# Schematic_STM32.net
KiCad netlist of a schematic drawn in Altium Designer
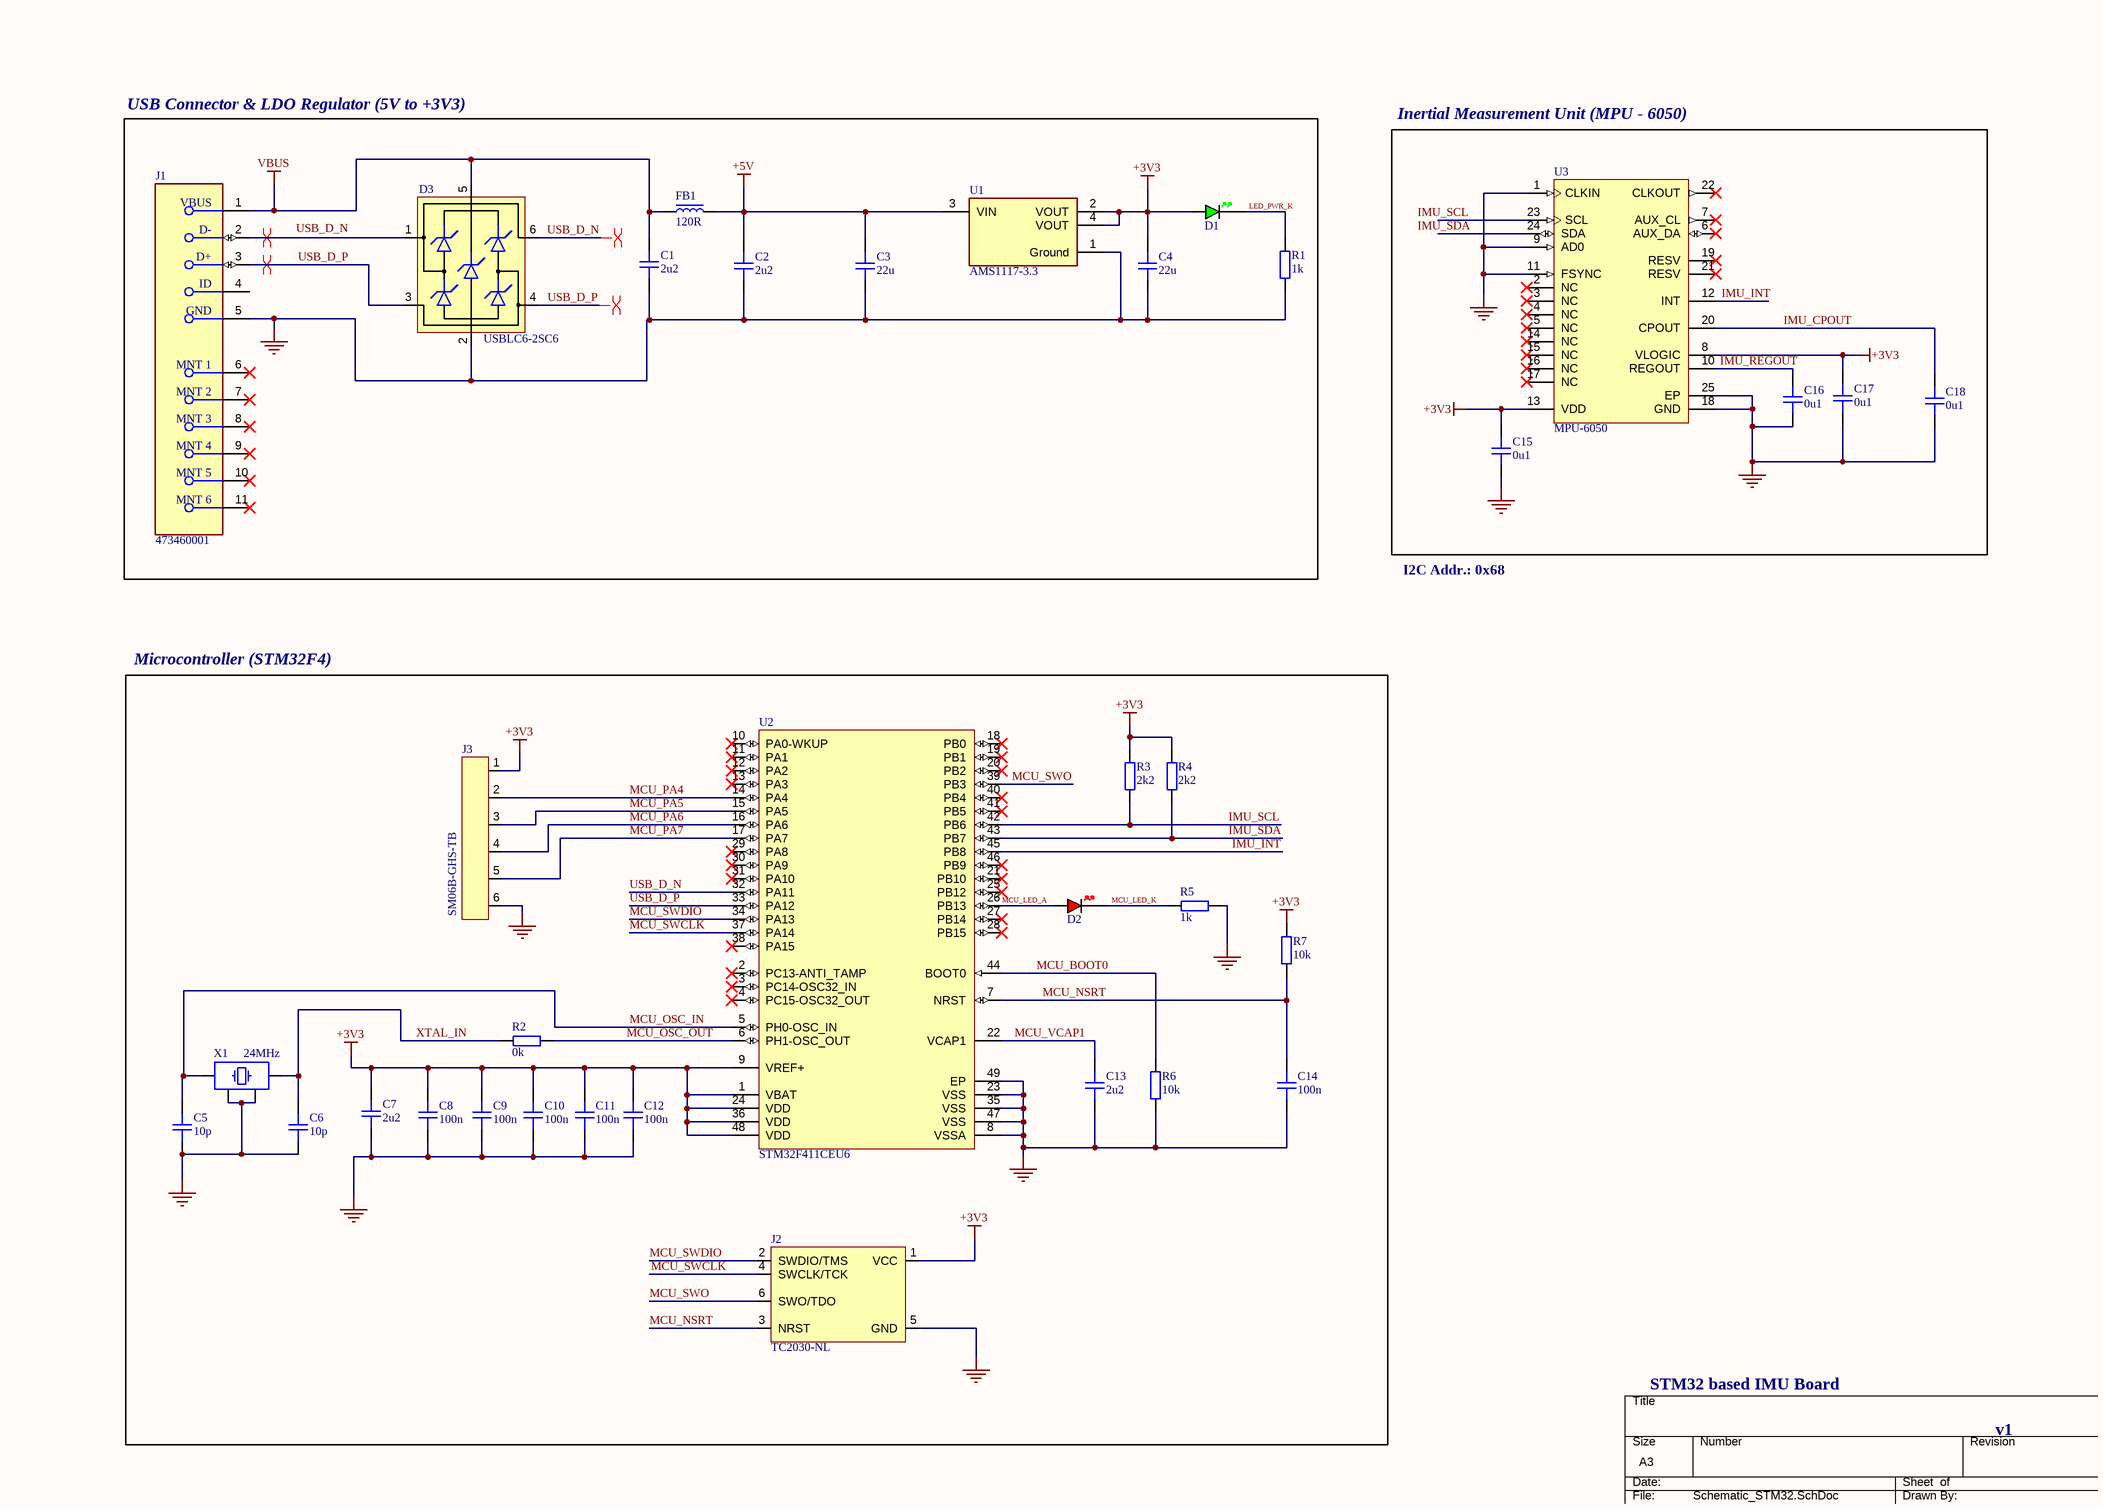
[diagram p0: Schematic_STM32.SchDoc]

(export (version "E")
  (design (tool "Eeschema 10.0.6"))
  (components
    (comp (ref "C1")
      (value "2u2")
      (footprint "CAP_0603")
      (description "Capacitor SMD 0603")
      (libsource (lib "Schematic-Lib-PhilsLab") (part "CAP_0603"))
    )
    (comp (ref "C2")
      (value "2u2")
      (footprint "CAP_0603")
      (description "Capacitor SMD 0603")
      (libsource (lib "Schematic-Lib-PhilsLab") (part "CAP_0603"))
    )
    (comp (ref "C3")
      (value "22u")
      (footprint "CAP_0805")
      (description "Capacitor SMD 0805")
      (libsource (lib "Schematic-Lib-PhilsLab") (part "CAP_0805"))
    )
    (comp (ref "C4")
      (value "22u")
      (footprint "CAP_0805")
      (description "Capacitor SMD 0805")
      (libsource (lib "Schematic-Lib-PhilsLab") (part "CAP_0805"))
    )
    (comp (ref "C5")
      (value "10p")
      (footprint "CAP_0402")
      (description "Capacitor SMD 0402")
      (libsource (lib "Schematic-Lib-PhilsLab") (part "CAP_0402"))
    )
    (comp (ref "C6")
      (value "10p")
      (footprint "CAP_0402")
      (description "Capacitor SMD 0402")
      (libsource (lib "Schematic-Lib-PhilsLab") (part "CAP_0402"))
    )
    (comp (ref "C7")
      (value "2u2")
      (footprint "CAP_0603")
      (description "Capacitor SMD 0603")
      (libsource (lib "Schematic-Lib-PhilsLab") (part "CAP_0603"))
    )
    (comp (ref "C8")
      (value "100n")
      (footprint "CAP_0402")
      (description "Capacitor SMD 0402")
      (libsource (lib "Schematic-Lib-PhilsLab") (part "CAP_0402"))
    )
    (comp (ref "C9")
      (value "100n")
      (footprint "CAP_0402")
      (description "Capacitor SMD 0402")
      (libsource (lib "Schematic-Lib-PhilsLab") (part "CAP_0402"))
    )
    (comp (ref "C10")
      (value "100n")
      (footprint "CAP_0402")
      (description "Capacitor SMD 0402")
      (libsource (lib "Schematic-Lib-PhilsLab") (part "CAP_0402"))
    )
    (comp (ref "C11")
      (value "100n")
      (footprint "CAP_0402")
      (description "Capacitor SMD 0402")
      (libsource (lib "Schematic-Lib-PhilsLab") (part "CAP_0402"))
    )
    (comp (ref "C12")
      (value "100n")
      (footprint "CAP_0402")
      (description "Capacitor SMD 0402")
      (libsource (lib "Schematic-Lib-PhilsLab") (part "CAP_0402"))
    )
    (comp (ref "C13")
      (value "2u2")
      (footprint "CAP_0603")
      (description "Capacitor SMD 0603")
      (libsource (lib "Schematic-Lib-PhilsLab") (part "CAP_0603"))
    )
    (comp (ref "C14")
      (value "100n")
      (footprint "CAP_0402")
      (description "Capacitor SMD 0402")
      (libsource (lib "Schematic-Lib-PhilsLab") (part "CAP_0402"))
    )
    (comp (ref "C15")
      (value "0u1")
      (footprint "CAP_0402")
      (description "Capacitor SMD 0402")
      (libsource (lib "Schematic-Lib-PhilsLab") (part "CAP_0402"))
    )
    (comp (ref "C16")
      (value "0u1")
      (footprint "CAP_0402")
      (description "Capacitor SMD 0402")
      (libsource (lib "Schematic-Lib-PhilsLab") (part "CAP_0402"))
    )
    (comp (ref "C17")
      (value "0u1")
      (footprint "CAP_0402")
      (description "Capacitor SMD 0402")
      (libsource (lib "Schematic-Lib-PhilsLab") (part "CAP_0402"))
    )
    (comp (ref "C18")
      (value "0u1")
      (footprint "CAP_0402")
      (description "Capacitor SMD 0402")
      (libsource (lib "Schematic-Lib-PhilsLab") (part "CAP_0402"))
    )
    (comp (ref "D1")
      (value "GREEN")
      (footprint "LED_0402_GREEN")
      (description "LED 0402 GREEN SMD")
      (libsource (lib "Schematic-Lib-PhilsLab") (part "LED_0402_GREEN"))
    )
    (comp (ref "D2")
      (value "RED")
      (footprint "LED_0402_RED")
      (description "LED 0402 RED SMD")
      (libsource (lib "Schematic-Lib-PhilsLab") (part "LED_0402_RED"))
    )
    (comp (ref "D3")
      (value "USBLC6-2SC6")
      (footprint "SOT-23-6")
      (description "Low-Capacitance ESD Protection USB")
      (fields (field (name "MANUFACTURER") "STMicroelectronics"))
      (libsource (lib "Schematic-Lib-PhilsLab") (part "USBLC6-2SC6"))
    )
    (comp (ref "FB1")
      (value "120R")
      (footprint "FB_0402")
      (description "Ferrite Bead SMD 0402")
      (libsource (lib "Schematic-Lib-PhilsLab") (part "FB_0402"))
    )
    (comp (ref "J1")
      (value "473460001")
      (footprint "FP-473460001-MFG")
      (description "CONN RCPT USB2.0 MICRO B SMD R/A")
      (fields
        (field (name "OCTOPART") "https://octopart.com/47346-0001-molex-7164928")
        (field (name "MANUFACTURER") "Molex")
      )
      (libsource (lib "Altium Content Vault") (part "53ae1f1d9b557310b43ca686e5bb76a"))
    )
    (comp (ref "J2")
      (value "TC2030-NL")
      (footprint "TC2030-NL-FP")
      (description "Tag-Connect No-Solder SWD Debug Connector (No Legs) DO NOT PLACE")
      (fields
        (field (name "MANUFACTURER") "Tag-Connect")
        (field (name "MANUFACTURER PART NUMBER") "TC2030-NL-FP")
      )
      (libsource (lib "Schematic-Lib-PhilsLab") (part "TC2030-NL"))
    )
    (comp (ref "J3")
      (value "SM06B-GHS-TB")
      (footprint "SM06B-GHS-TB")
      (description "Header Connector 6 Position 1.25MM Pitch SMD Horizontal JST GH")
      (fields (field (name "MANUFACTURER") "JST"))
      (libsource (lib "Schematic-Lib-PhilsLab") (part "SM06B-GHS-TB"))
    )
    (comp (ref "R1")
      (value "1k")
      (footprint "RES_0402")
      (description "Resistor SMD 0402")
      (libsource (lib "Schematic-Lib-PhilsLab") (part "RES_0402"))
    )
    (comp (ref "R2")
      (value "0k")
      (footprint "RES_0402")
      (description "Resistor SMD 0402")
      (libsource (lib "Schematic-Lib-PhilsLab") (part "RES_0402"))
    )
    (comp (ref "R3")
      (value "2k2")
      (footprint "RES_0402")
      (description "Resistor SMD 0402")
      (libsource (lib "Schematic-Lib-PhilsLab") (part "RES_0402"))
    )
    (comp (ref "R4")
      (value "2k2")
      (footprint "RES_0402")
      (description "Resistor SMD 0402")
      (libsource (lib "Schematic-Lib-PhilsLab") (part "RES_0402"))
    )
    (comp (ref "R5")
      (value "1k")
      (footprint "RES_0402")
      (description "Resistor SMD 0402")
      (libsource (lib "Schematic-Lib-PhilsLab") (part "RES_0402"))
    )
    (comp (ref "R6")
      (value "10k")
      (footprint "RES_0402")
      (description "Resistor SMD 0402")
      (libsource (lib "Schematic-Lib-PhilsLab") (part "RES_0402"))
    )
    (comp (ref "R7")
      (value "10k")
      (footprint "RES_0402")
      (description "Resistor SMD 0402")
      (libsource (lib "Schematic-Lib-PhilsLab") (part "RES_0402"))
    )
    (comp (ref "U1")
      (value "AMS1117-3.3")
      (footprint "FP-AMS1117-IPC_C")
      (description "LDO Voltage Regulators 1A, 3.3V")
      (fields
        (field (name "OCTOPART") "https://octopart.com/ams1117-3.3-advanced+monolithic+systems-25899300")
        (field (name "MANUFACTURER") "Advanced Monolithic Systems")
      )
      (libsource (lib "Altium Content Vault") (part "8bdbb5f8e77002000e30dd2845d0354"))
    )
    (comp (ref "U2")
      (value "STM32F411CEU6")
      (footprint "STM-UFQFPN48_L")
      (libsource (lib "Altium Content Vault") (part "MC-ARM-STM32F411-UFQFPN48"))
    )
    (comp (ref "U3")
      (value "MPU-6050")
      (footprint "IS-QFN-24_V")
      (fields (field (name "MANUFACTURER") "InvenSense"))
      (libsource (lib "Altium Content Vault") (part "IS-MPU-6050-QFN-24"))
    )
    (comp (ref "X1")
      (value "24MHz")
      (footprint "XTAL_3225")
      (description "Crystal SMD 24MHz 10PPM 7pF 3225")
      (fields
        (field (name "MANUFACTURER") "Epson")
        (field (name "MANUFACTURER PART NUMBER") "TSX-3225 24.0000MF15X-AC")
      )
      (libsource (lib "Schematic-Lib-PhilsLab") (part "TSX-3225_24.0000MF15X-AC"))
    )
  )
  (nets
    (net (code "1") (name "+3V3") (class "Default")
      (node (ref "C10") (pin "2") (pinfunction "2_2") (pintype "passive"))
      (node (ref "C11") (pin "2") (pinfunction "2_2") (pintype "passive"))
      (node (ref "C12") (pin "2") (pinfunction "2_2") (pintype "passive"))
      (node (ref "C15") (pin "2") (pinfunction "2_2") (pintype "passive"))
      (node (ref "C17") (pin "2") (pinfunction "2_2") (pintype "passive"))
      (node (ref "C4") (pin "2") (pinfunction "2_2") (pintype "passive"))
      (node (ref "C7") (pin "2") (pinfunction "2_2") (pintype "passive"))
      (node (ref "C8") (pin "2") (pinfunction "2_2") (pintype "passive"))
      (node (ref "C9") (pin "2") (pinfunction "2_2") (pintype "passive"))
      (node (ref "D1") (pin "A") (pinfunction "A_A") (pintype "passive"))
      (node (ref "J2") (pin "1") (pinfunction "VCC_1") (pintype "passive"))
      (node (ref "J3") (pin "1") (pinfunction "1_1") (pintype "passive"))
      (node (ref "R3") (pin "2") (pinfunction "2_2") (pintype "passive"))
      (node (ref "R4") (pin "2") (pinfunction "2_2") (pintype "passive"))
      (node (ref "R7") (pin "2") (pinfunction "2_2") (pintype "passive"))
      (node (ref "U1") (pin "2") (pinfunction "VOUT_2") (pintype "passive"))
      (node (ref "U1") (pin "4") (pinfunction "VOUT_4") (pintype "passive"))
      (node (ref "U2") (pin "1") (pinfunction "VBAT_1") (pintype "power_in"))
      (node (ref "U2") (pin "24") (pinfunction "VDD_24") (pintype "power_in"))
      (node (ref "U2") (pin "36") (pinfunction "VDD_36") (pintype "power_in"))
      (node (ref "U2") (pin "48") (pinfunction "VDD_48") (pintype "power_in"))
      (node (ref "U2") (pin "9") (pinfunction "VREF+_9") (pintype "power_in"))
      (node (ref "U3") (pin "13") (pinfunction "VDD_13") (pintype "power_in"))
      (node (ref "U3") (pin "8") (pinfunction "VLOGIC_8") (pintype "power_in"))
    )
    (net (code "2") (name "+5V") (class "Default")
      (node (ref "C2") (pin "2") (pinfunction "2_2") (pintype "passive"))
      (node (ref "C3") (pin "2") (pinfunction "2_2") (pintype "passive"))
      (node (ref "FB1") (pin "2") (pinfunction "2_2") (pintype "passive"))
      (node (ref "U1") (pin "3") (pinfunction "VIN_3") (pintype "power_in"))
    )
    (net (code "3") (name "/IMU_CPOUT") (class "Default")
      (node (ref "C18") (pin "2") (pinfunction "2_2") (pintype "passive"))
      (node (ref "U3") (pin "20") (pinfunction "CPOUT_20") (pintype "passive"))
    )
    (net (code "4") (name "/IMU_INT") (class "Default")
      (node (ref "U2") (pin "45") (pinfunction "PB8_45") (pintype "bidirectional"))
      (node (ref "U3") (pin "12") (pinfunction "INT_12") (pintype "open_collector"))
    )
    (net (code "5") (name "/IMU_REGOUT") (class "Default")
      (node (ref "C16") (pin "2") (pinfunction "2_2") (pintype "passive"))
      (node (ref "U3") (pin "10") (pinfunction "REGOUT_10") (pintype "passive"))
    )
    (net (code "6") (name "/IMU_SCL") (class "Default")
      (node (ref "R3") (pin "1") (pinfunction "1_1") (pintype "passive"))
      (node (ref "U2") (pin "42") (pinfunction "PB6_42") (pintype "bidirectional"))
      (node (ref "U3") (pin "23") (pinfunction "SCL_23") (pintype "input"))
    )
    (net (code "7") (name "/IMU_SDA") (class "Default")
      (node (ref "R4") (pin "1") (pinfunction "1_1") (pintype "passive"))
      (node (ref "U2") (pin "43") (pinfunction "PB7_43") (pintype "bidirectional"))
      (node (ref "U3") (pin "24") (pinfunction "SDA_24") (pintype "bidirectional"))
    )
    (net (code "8") (name "/LED_PWR_K") (class "Default")
      (node (ref "D1") (pin "K") (pinfunction "K_K") (pintype "passive"))
      (node (ref "R1") (pin "2") (pinfunction "2_2") (pintype "passive"))
    )
    (net (code "9") (name "/MCU_BOOT0") (class "Default")
      (node (ref "R6") (pin "2") (pinfunction "2_2") (pintype "passive"))
      (node (ref "U2") (pin "44") (pinfunction "BOOT0_44") (pintype "input"))
    )
    (net (code "10") (name "/MCU_LED_A") (class "Default")
      (node (ref "D2") (pin "A") (pinfunction "A_A") (pintype "passive"))
      (node (ref "U2") (pin "26") (pinfunction "PB13_26") (pintype "bidirectional"))
    )
    (net (code "11") (name "/MCU_LED_K") (class "Default")
      (node (ref "D2") (pin "K") (pinfunction "K_K") (pintype "passive"))
      (node (ref "R5") (pin "2") (pinfunction "2_2") (pintype "passive"))
    )
    (net (code "12") (name "/MCU_NSRT") (class "Default")
      (node (ref "C14") (pin "2") (pinfunction "2_2") (pintype "passive"))
      (node (ref "J2") (pin "3") (pinfunction "NRST_3") (pintype "passive"))
      (node (ref "R7") (pin "1") (pinfunction "1_1") (pintype "passive"))
      (node (ref "U2") (pin "7") (pinfunction "NRST_7") (pintype "bidirectional"))
    )
    (net (code "13") (name "/MCU_OSC_IN") (class "Default")
      (node (ref "C5") (pin "2") (pinfunction "2_2") (pintype "passive"))
      (node (ref "U2") (pin "5") (pinfunction "PH0-OSC_IN_5") (pintype "bidirectional"))
      (node (ref "X1") (pin "1") (pinfunction "1_1") (pintype "passive"))
    )
    (net (code "14") (name "/MCU_OSC_OUT") (class "Default")
      (node (ref "R2") (pin "1") (pinfunction "1_1") (pintype "passive"))
      (node (ref "U2") (pin "6") (pinfunction "PH1-OSC_OUT_6") (pintype "bidirectional"))
    )
    (net (code "15") (name "/MCU_PA4") (class "Default")
      (node (ref "J3") (pin "2") (pinfunction "2_2") (pintype "passive"))
      (node (ref "U2") (pin "14") (pinfunction "PA4_14") (pintype "bidirectional"))
    )
    (net (code "16") (name "/MCU_PA5") (class "Default")
      (node (ref "J3") (pin "3") (pinfunction "3_3") (pintype "passive"))
      (node (ref "U2") (pin "15") (pinfunction "PA5_15") (pintype "bidirectional"))
    )
    (net (code "17") (name "/MCU_PA6") (class "Default")
      (node (ref "J3") (pin "4") (pinfunction "4_4") (pintype "passive"))
      (node (ref "U2") (pin "16") (pinfunction "PA6_16") (pintype "bidirectional"))
    )
    (net (code "18") (name "/MCU_PA7") (class "Default")
      (node (ref "J3") (pin "5") (pinfunction "5_5") (pintype "passive"))
      (node (ref "U2") (pin "17") (pinfunction "PA7_17") (pintype "bidirectional"))
    )
    (net (code "19") (name "/MCU_SWCLK") (class "Default")
      (node (ref "J2") (pin "4") (pinfunction "SWCLK/TCK_4") (pintype "passive"))
      (node (ref "U2") (pin "37") (pinfunction "PA14_37") (pintype "bidirectional"))
    )
    (net (code "20") (name "/MCU_SWDIO") (class "Default")
      (node (ref "J2") (pin "2") (pinfunction "SWDIO/TMS_2") (pintype "passive"))
      (node (ref "U2") (pin "34") (pinfunction "PA13_34") (pintype "bidirectional"))
    )
    (net (code "21") (name "/MCU_SWO") (class "Default")
      (node (ref "J2") (pin "6") (pinfunction "SWO/TDO_6") (pintype "passive"))
      (node (ref "U2") (pin "39") (pinfunction "PB3_39") (pintype "bidirectional"))
    )
    (net (code "22") (name "/MCU_VCAP1") (class "Default")
      (node (ref "C13") (pin "2") (pinfunction "2_2") (pintype "passive"))
      (node (ref "U2") (pin "22") (pinfunction "VCAP1_22") (pintype "passive"))
    )
    (net (code "23") (name "/USB_D_N") (class "Default")
      (node (ref "D3") (pin "6") (pinfunction "IO1_6") (pintype "bidirectional"))
      (node (ref "U2") (pin "32") (pinfunction "PA11_32") (pintype "bidirectional"))
    )
    (net (code "24") (name "/USB_D_P") (class "Default")
      (node (ref "D3") (pin "3") (pinfunction "IO2_3") (pintype "bidirectional"))
      (node (ref "D3") (pin "4") (pinfunction "IO2_4") (pintype "bidirectional"))
      (node (ref "J1") (pin "3") (pinfunction "D+_3") (pintype "bidirectional"))
      (node (ref "U2") (pin "33") (pinfunction "PA12_33") (pintype "bidirectional"))
    )
    (net (code "25") (name "/XTAL_IN") (class "Default")
      (node (ref "C6") (pin "2") (pinfunction "2_2") (pintype "passive"))
      (node (ref "R2") (pin "2") (pinfunction "2_2") (pintype "passive"))
      (node (ref "X1") (pin "3") (pinfunction "3_3") (pintype "passive"))
    )
    (net (code "26") (name "GND") (class "Default")
      (node (ref "C1") (pin "1") (pinfunction "1_1") (pintype "passive"))
      (node (ref "C10") (pin "1") (pinfunction "1_1") (pintype "passive"))
      (node (ref "C11") (pin "1") (pinfunction "1_1") (pintype "passive"))
      (node (ref "C12") (pin "1") (pinfunction "1_1") (pintype "passive"))
      (node (ref "C13") (pin "1") (pinfunction "1_1") (pintype "passive"))
      (node (ref "C14") (pin "1") (pinfunction "1_1") (pintype "passive"))
      (node (ref "C15") (pin "1") (pinfunction "1_1") (pintype "passive"))
      (node (ref "C16") (pin "1") (pinfunction "1_1") (pintype "passive"))
      (node (ref "C17") (pin "1") (pinfunction "1_1") (pintype "passive"))
      (node (ref "C18") (pin "1") (pinfunction "1_1") (pintype "passive"))
      (node (ref "C2") (pin "1") (pinfunction "1_1") (pintype "passive"))
      (node (ref "C3") (pin "1") (pinfunction "1_1") (pintype "passive"))
      (node (ref "C4") (pin "1") (pinfunction "1_1") (pintype "passive"))
      (node (ref "C5") (pin "1") (pinfunction "1_1") (pintype "passive"))
      (node (ref "C6") (pin "1") (pinfunction "1_1") (pintype "passive"))
      (node (ref "C7") (pin "1") (pinfunction "1_1") (pintype "passive"))
      (node (ref "C8") (pin "1") (pinfunction "1_1") (pintype "passive"))
      (node (ref "C9") (pin "1") (pinfunction "1_1") (pintype "passive"))
      (node (ref "D3") (pin "2") (pinfunction "GND_2") (pintype "power_in"))
      (node (ref "J1") (pin "5") (pinfunction "GND_5") (pintype "power_in"))
      (node (ref "J2") (pin "5") (pinfunction "GND_5") (pintype "passive"))
      (node (ref "J3") (pin "6") (pinfunction "6_6") (pintype "passive"))
      (node (ref "R1") (pin "1") (pinfunction "1_1") (pintype "passive"))
      (node (ref "R5") (pin "1") (pinfunction "1_1") (pintype "passive"))
      (node (ref "R6") (pin "1") (pinfunction "1_1") (pintype "passive"))
      (node (ref "U1") (pin "1") (pinfunction "Ground_1") (pintype "power_in"))
      (node (ref "U2") (pin "23") (pinfunction "VSS_23") (pintype "power_in"))
      (node (ref "U2") (pin "35") (pinfunction "VSS_35") (pintype "power_in"))
      (node (ref "U2") (pin "47") (pinfunction "VSS_47") (pintype "power_in"))
      (node (ref "U2") (pin "49") (pinfunction "EP_49") (pintype "power_in"))
      (node (ref "U2") (pin "8") (pinfunction "VSSA_8") (pintype "power_in"))
      (node (ref "U3") (pin "1") (pinfunction "CLKIN_1") (pintype "input"))
      (node (ref "U3") (pin "11") (pinfunction "FSYNC_11") (pintype "input"))
      (node (ref "U3") (pin "18") (pinfunction "GND_18") (pintype "power_in"))
      (node (ref "U3") (pin "25") (pinfunction "EP_25") (pintype "power_in"))
      (node (ref "U3") (pin "9") (pinfunction "AD0_9") (pintype "input"))
      (node (ref "X1") (pin "2") (pinfunction "2_2") (pintype "passive"))
      (node (ref "X1") (pin "4") (pinfunction "4_4") (pintype "passive"))
    )
    (net (code "27") (name "Net-(J1-D-)") (class "Default")
      (node (ref "D3") (pin "1") (pinfunction "IO1_1") (pintype "bidirectional"))
      (node (ref "J1") (pin "2") (pinfunction "D-_2") (pintype "bidirectional"))
    )
    (net (code "28") (name "VBUS") (class "Default")
      (node (ref "C1") (pin "2") (pinfunction "2_2") (pintype "passive"))
      (node (ref "D3") (pin "5") (pinfunction "VBUS_5") (pintype "power_in"))
      (node (ref "FB1") (pin "1") (pinfunction "1_1") (pintype "passive"))
      (node (ref "J1") (pin "1") (pinfunction "VBUS_1") (pintype "power_in"))
    )
    (net (code "29") (name "unconnected-(J1-ID-Pad4)") (class "Default")
      (node (ref "J1") (pin "4") (pinfunction "ID_4") (pintype "passive"))
    )
    (net (code "30") (name "unconnected-(J1-MNT_1-Pad6)") (class "Default")
      (node (ref "J1") (pin "6") (pinfunction "MNT_1_6") (pintype "passive+no_connect"))
    )
    (net (code "31") (name "unconnected-(J1-MNT_2-Pad7)") (class "Default")
      (node (ref "J1") (pin "7") (pinfunction "MNT_2_7") (pintype "passive+no_connect"))
    )
    (net (code "32") (name "unconnected-(J1-MNT_3-Pad8)") (class "Default")
      (node (ref "J1") (pin "8") (pinfunction "MNT_3_8") (pintype "passive+no_connect"))
    )
    (net (code "33") (name "unconnected-(J1-MNT_4-Pad9)") (class "Default")
      (node (ref "J1") (pin "9") (pinfunction "MNT_4_9") (pintype "passive+no_connect"))
    )
    (net (code "34") (name "unconnected-(J1-MNT_5-Pad10)") (class "Default")
      (node (ref "J1") (pin "10") (pinfunction "MNT_5_10") (pintype "passive+no_connect"))
    )
    (net (code "35") (name "unconnected-(J1-MNT_6-Pad11)") (class "Default")
      (node (ref "J1") (pin "11") (pinfunction "MNT_6_11") (pintype "passive+no_connect"))
    )
    (net (code "36") (name "unconnected-(U2-PA0-WKUP-Pad10)") (class "Default")
      (node (ref "U2") (pin "10") (pinfunction "PA0-WKUP_10") (pintype "bidirectional+no_connect"))
    )
    (net (code "37") (name "unconnected-(U2-PA1-Pad11)") (class "Default")
      (node (ref "U2") (pin "11") (pinfunction "PA1_11") (pintype "bidirectional+no_connect"))
    )
    (net (code "38") (name "unconnected-(U2-PA2-Pad12)") (class "Default")
      (node (ref "U2") (pin "12") (pinfunction "PA2_12") (pintype "bidirectional+no_connect"))
    )
    (net (code "39") (name "unconnected-(U2-PA3-Pad13)") (class "Default")
      (node (ref "U2") (pin "13") (pinfunction "PA3_13") (pintype "bidirectional+no_connect"))
    )
    (net (code "40") (name "unconnected-(U2-PA8-Pad29)") (class "Default")
      (node (ref "U2") (pin "29") (pinfunction "PA8_29") (pintype "bidirectional+no_connect"))
    )
    (net (code "41") (name "unconnected-(U2-PA9-Pad30)") (class "Default")
      (node (ref "U2") (pin "30") (pinfunction "PA9_30") (pintype "bidirectional+no_connect"))
    )
    (net (code "42") (name "unconnected-(U2-PA10-Pad31)") (class "Default")
      (node (ref "U2") (pin "31") (pinfunction "PA10_31") (pintype "bidirectional+no_connect"))
    )
    (net (code "43") (name "unconnected-(U2-PA15-Pad38)") (class "Default")
      (node (ref "U2") (pin "38") (pinfunction "PA15_38") (pintype "bidirectional+no_connect"))
    )
    (net (code "44") (name "unconnected-(U2-PB0-Pad18)") (class "Default")
      (node (ref "U2") (pin "18") (pinfunction "PB0_18") (pintype "bidirectional+no_connect"))
    )
    (net (code "45") (name "unconnected-(U2-PB1-Pad19)") (class "Default")
      (node (ref "U2") (pin "19") (pinfunction "PB1_19") (pintype "bidirectional+no_connect"))
    )
    (net (code "46") (name "unconnected-(U2-PB2-Pad20)") (class "Default")
      (node (ref "U2") (pin "20") (pinfunction "PB2_20") (pintype "bidirectional+no_connect"))
    )
    (net (code "47") (name "unconnected-(U2-PB4-Pad40)") (class "Default")
      (node (ref "U2") (pin "40") (pinfunction "PB4_40") (pintype "bidirectional+no_connect"))
    )
    (net (code "48") (name "unconnected-(U2-PB5-Pad41)") (class "Default")
      (node (ref "U2") (pin "41") (pinfunction "PB5_41") (pintype "bidirectional+no_connect"))
    )
    (net (code "49") (name "unconnected-(U2-PB9-Pad46)") (class "Default")
      (node (ref "U2") (pin "46") (pinfunction "PB9_46") (pintype "bidirectional+no_connect"))
    )
    (net (code "50") (name "unconnected-(U2-PB10-Pad21)") (class "Default")
      (node (ref "U2") (pin "21") (pinfunction "PB10_21") (pintype "bidirectional+no_connect"))
    )
    (net (code "51") (name "unconnected-(U2-PB12-Pad25)") (class "Default")
      (node (ref "U2") (pin "25") (pinfunction "PB12_25") (pintype "bidirectional+no_connect"))
    )
    (net (code "52") (name "unconnected-(U2-PB14-Pad27)") (class "Default")
      (node (ref "U2") (pin "27") (pinfunction "PB14_27") (pintype "bidirectional+no_connect"))
    )
    (net (code "53") (name "unconnected-(U2-PB15-Pad28)") (class "Default")
      (node (ref "U2") (pin "28") (pinfunction "PB15_28") (pintype "bidirectional+no_connect"))
    )
    (net (code "54") (name "unconnected-(U2-PC13-ANTI_TAMP-Pad2)") (class "Default")
      (node (ref "U2") (pin "2") (pinfunction "PC13-ANTI_TAMP_2") (pintype "bidirectional+no_connect"))
    )
    (net (code "55") (name "unconnected-(U2-PC14-OSC32_IN-Pad3)") (class "Default")
      (node (ref "U2") (pin "3") (pinfunction "PC14-OSC32_IN_3") (pintype "bidirectional+no_connect"))
    )
    (net (code "56") (name "unconnected-(U2-PC15-OSC32_OUT-Pad4)") (class "Default")
      (node (ref "U2") (pin "4") (pinfunction "PC15-OSC32_OUT_4") (pintype "bidirectional+no_connect"))
    )
    (net (code "57") (name "unconnected-(U3-AUX_CL-Pad7)") (class "Default")
      (node (ref "U3") (pin "7") (pinfunction "AUX_CL_7") (pintype "output+no_connect"))
    )
    (net (code "58") (name "unconnected-(U3-AUX_DA-Pad6)") (class "Default")
      (node (ref "U3") (pin "6") (pinfunction "AUX_DA_6") (pintype "bidirectional+no_connect"))
    )
    (net (code "59") (name "unconnected-(U3-CLKOUT-Pad22)") (class "Default")
      (node (ref "U3") (pin "22") (pinfunction "CLKOUT_22") (pintype "output+no_connect"))
    )
    (net (code "60") (name "unconnected-(U3-NC-Pad2)") (class "Default")
      (node (ref "U3") (pin "2") (pinfunction "NC_2") (pintype "passive+no_connect"))
    )
    (net (code "61") (name "unconnected-(U3-NC-Pad3)") (class "Default")
      (node (ref "U3") (pin "3") (pinfunction "NC_3") (pintype "passive+no_connect"))
    )
    (net (code "62") (name "unconnected-(U3-NC-Pad4)") (class "Default")
      (node (ref "U3") (pin "4") (pinfunction "NC_4") (pintype "passive+no_connect"))
    )
    (net (code "63") (name "unconnected-(U3-NC-Pad5)") (class "Default")
      (node (ref "U3") (pin "5") (pinfunction "NC_5") (pintype "passive+no_connect"))
    )
    (net (code "64") (name "unconnected-(U3-NC-Pad14)") (class "Default")
      (node (ref "U3") (pin "14") (pinfunction "NC_14") (pintype "passive+no_connect"))
    )
    (net (code "65") (name "unconnected-(U3-NC-Pad15)") (class "Default")
      (node (ref "U3") (pin "15") (pinfunction "NC_15") (pintype "passive+no_connect"))
    )
    (net (code "66") (name "unconnected-(U3-NC-Pad16)") (class "Default")
      (node (ref "U3") (pin "16") (pinfunction "NC_16") (pintype "passive+no_connect"))
    )
    (net (code "67") (name "unconnected-(U3-NC-Pad17)") (class "Default")
      (node (ref "U3") (pin "17") (pinfunction "NC_17") (pintype "passive+no_connect"))
    )
    (net (code "68") (name "unconnected-(U3-RESV-Pad19)") (class "Default")
      (node (ref "U3") (pin "19") (pinfunction "RESV_19") (pintype "passive+no_connect"))
    )
    (net (code "69") (name "unconnected-(U3-RESV-Pad21)") (class "Default")
      (node (ref "U3") (pin "21") (pinfunction "RESV_21") (pintype "passive+no_connect"))
    )
  )
)
